# 780-00012-P2_rev3_Sch_M2_Focus_Drive.net
KiCad netlist of a schematic drawn in Altium Designer
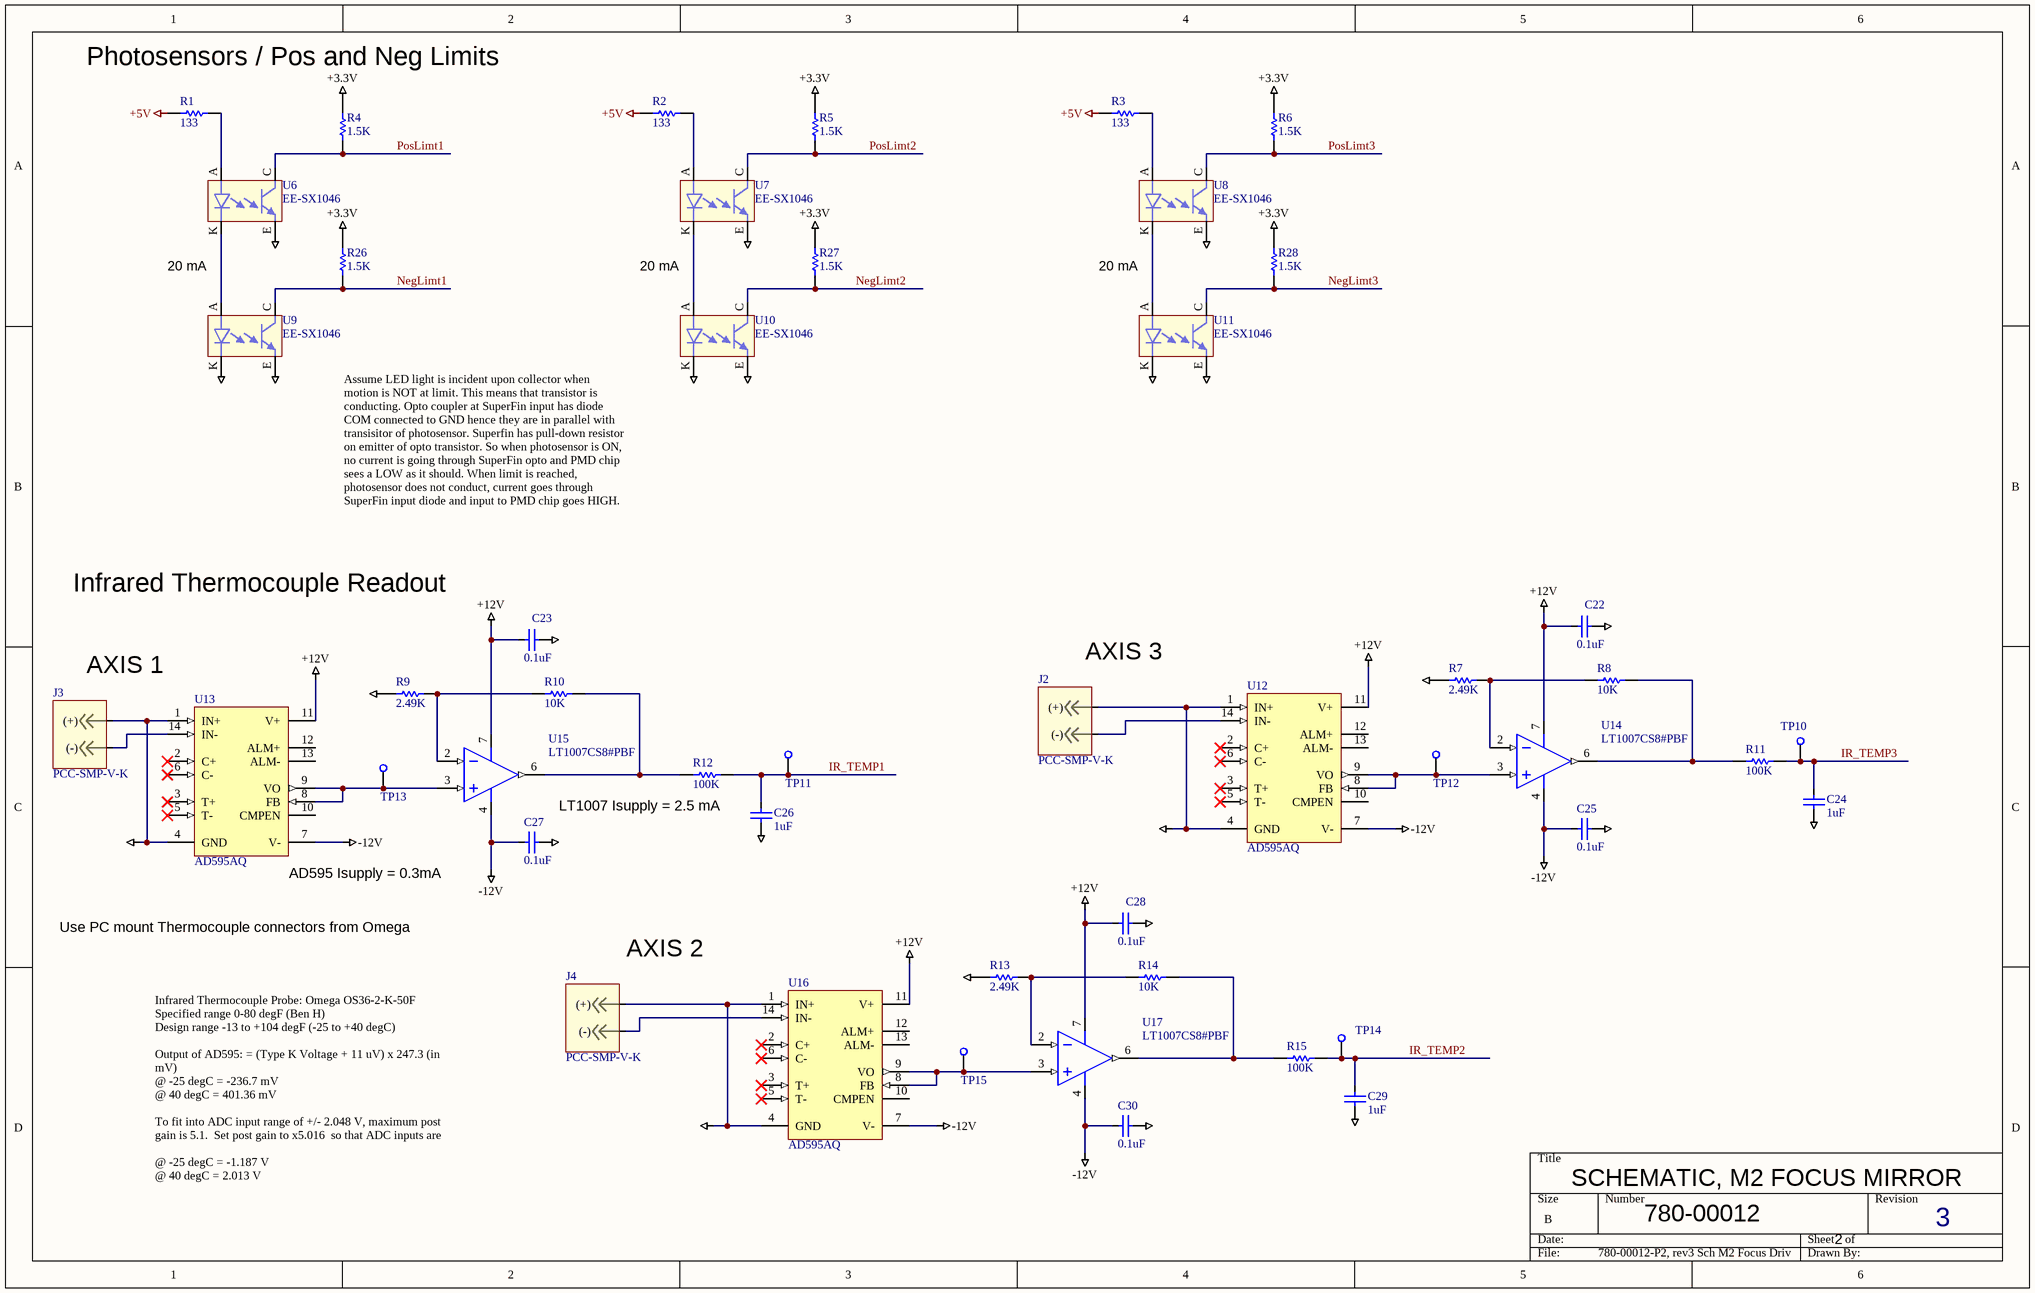
[diagram p0: 780-00012-P2, rev3 Sch M2 Focus Drive.SchDoc]

(export (version "E")
  (design (tool "Eeschema 10.0.6"))
  (components
    (comp (ref "C22")
      (value "0.1uF")
      (footprint "SMD_0805")
      (description "Capacitor")
      (fields (field (name "Comment") "Cap SMD"))
      (libsource (lib "Richs Schematic Components") (part "Cap SMD"))
    )
    (comp (ref "C23")
      (value "0.1uF")
      (footprint "SMD_0805")
      (description "Capacitor")
      (fields (field (name "Comment") "Cap SMD"))
      (libsource (lib "Richs Schematic Components") (part "Cap SMD"))
    )
    (comp (ref "C24")
      (value "1uF")
      (footprint "SMD_0805")
      (description "Capacitor")
      (fields (field (name "Comment") "Cap SMD"))
      (libsource (lib "Richs Schematic Components") (part "Cap SMD"))
    )
    (comp (ref "C25")
      (value "0.1uF")
      (footprint "SMD_0805")
      (description "Capacitor")
      (fields (field (name "Comment") "Cap SMD"))
      (libsource (lib "Richs Schematic Components") (part "Cap SMD"))
    )
    (comp (ref "C26")
      (value "1uF")
      (footprint "SMD_0805")
      (description "Capacitor")
      (fields (field (name "Comment") "Cap SMD"))
      (libsource (lib "Richs Schematic Components") (part "Cap SMD"))
    )
    (comp (ref "C27")
      (value "0.1uF")
      (footprint "SMD_0805")
      (description "Capacitor")
      (fields (field (name "Comment") "Cap SMD"))
      (libsource (lib "Richs Schematic Components") (part "Cap SMD"))
    )
    (comp (ref "C28")
      (value "0.1uF")
      (footprint "SMD_0805")
      (description "Capacitor")
      (fields (field (name "Comment") "Cap SMD"))
      (libsource (lib "Richs Schematic Components") (part "Cap SMD"))
    )
    (comp (ref "C29")
      (value "1uF")
      (footprint "SMD_0805")
      (description "Capacitor")
      (fields (field (name "Comment") "Cap SMD"))
      (libsource (lib "Richs Schematic Components") (part "Cap SMD"))
    )
    (comp (ref "C30")
      (value "0.1uF")
      (footprint "SMD_0805")
      (description "Capacitor")
      (fields (field (name "Comment") "Cap SMD"))
      (libsource (lib "Richs Schematic Components") (part "Cap SMD"))
    )
    (comp (ref "J2")
      (value "PCC-SMP-V-K")
      (footprint "THERMOCOUPLE")
      (description "T/C Conn PCB mount vertical")
      (libsource (lib "Richs Schematic Components") (part "Thermocouple Connector"))
    )
    (comp (ref "J3")
      (value "PCC-SMP-V-K")
      (footprint "THERMOCOUPLE")
      (description "T/C Conn PCB mount vertical")
      (libsource (lib "Richs Schematic Components") (part "Thermocouple Connector"))
    )
    (comp (ref "J4")
      (value "PCC-SMP-V-K")
      (footprint "THERMOCOUPLE")
      (description "T/C Conn PCB mount vertical")
      (libsource (lib "Richs Schematic Components") (part "Thermocouple Connector"))
    )
    (comp (ref "R1")
      (value "133")
      (footprint "SMD_0805")
      (description "Resistor 0805")
      (fields (field (name "MANUFACTURER") "Vishay/Dale") (field (name "Comment") "Res 0805"))
      (libsource (lib "Richs Schematic Components") (part "Res SMD"))
    )
    (comp (ref "R2")
      (value "133")
      (footprint "SMD_0805")
      (description "Resistor 0805")
      (fields (field (name "MANUFACTURER") "Vishay/Dale") (field (name "Comment") "Res 0805"))
      (libsource (lib "Richs Schematic Components") (part "Res SMD"))
    )
    (comp (ref "R3")
      (value "133")
      (footprint "SMD_0805")
      (description "Resistor 0805")
      (fields (field (name "MANUFACTURER") "Vishay/Dale") (field (name "Comment") "Res 0805"))
      (libsource (lib "Richs Schematic Components") (part "Res SMD"))
    )
    (comp (ref "R4")
      (value "1.5K")
      (footprint "SMD_0805")
      (description "Resistor 0805")
      (fields (field (name "MANUFACTURER") "Vishay/Dale") (field (name "Comment") "Res 0805"))
      (libsource (lib "Richs Schematic Components") (part "Res SMD"))
    )
    (comp (ref "R5")
      (value "1.5K")
      (footprint "SMD_0805")
      (description "Resistor 0805")
      (fields (field (name "MANUFACTURER") "Vishay/Dale") (field (name "Comment") "Res 0805"))
      (libsource (lib "Richs Schematic Components") (part "Res SMD"))
    )
    (comp (ref "R6")
      (value "1.5K")
      (footprint "SMD_0805")
      (description "Resistor 0805")
      (fields (field (name "MANUFACTURER") "Vishay/Dale") (field (name "Comment") "Res 0805"))
      (libsource (lib "Richs Schematic Components") (part "Res SMD"))
    )
    (comp (ref "R7")
      (value "2.49K")
      (footprint "SMD_0805")
      (description "Resistor 0805")
      (fields (field (name "MANUFACTURER") "Vishay/Dale") (field (name "Comment") "Res 0805"))
      (libsource (lib "Richs Schematic Components") (part "Res SMD"))
    )
    (comp (ref "R8")
      (value "10K")
      (footprint "SMD_0805")
      (description "Resistor 0805")
      (fields (field (name "MANUFACTURER") "Vishay/Dale") (field (name "Comment") "Res 0805"))
      (libsource (lib "Richs Schematic Components") (part "Res SMD"))
    )
    (comp (ref "R9")
      (value "2.49K")
      (footprint "SMD_0805")
      (description "Resistor 0805")
      (fields (field (name "MANUFACTURER") "Vishay/Dale") (field (name "Comment") "Res 0805"))
      (libsource (lib "Richs Schematic Components") (part "Res SMD"))
    )
    (comp (ref "R10")
      (value "10K")
      (footprint "SMD_0805")
      (description "Resistor 0805")
      (fields (field (name "MANUFACTURER") "Vishay/Dale") (field (name "Comment") "Res 0805"))
      (libsource (lib "Richs Schematic Components") (part "Res SMD"))
    )
    (comp (ref "R11")
      (value "100K")
      (footprint "SMD_0805")
      (description "Resistor 0805")
      (fields (field (name "MANUFACTURER") "Vishay/Dale") (field (name "Comment") "Res 0805"))
      (libsource (lib "Richs Schematic Components") (part "Res SMD"))
    )
    (comp (ref "R12")
      (value "100K")
      (footprint "SMD_0805")
      (description "Resistor 0805")
      (fields (field (name "MANUFACTURER") "Vishay/Dale") (field (name "Comment") "Res 0805"))
      (libsource (lib "Richs Schematic Components") (part "Res SMD"))
    )
    (comp (ref "R13")
      (value "2.49K")
      (footprint "SMD_0805")
      (description "Resistor 0805")
      (fields (field (name "MANUFACTURER") "Vishay/Dale") (field (name "Comment") "Res 0805"))
      (libsource (lib "Richs Schematic Components") (part "Res SMD"))
    )
    (comp (ref "R14")
      (value "10K")
      (footprint "SMD_0805")
      (description "Resistor 0805")
      (fields (field (name "MANUFACTURER") "Vishay/Dale") (field (name "Comment") "Res 0805"))
      (libsource (lib "Richs Schematic Components") (part "Res SMD"))
    )
    (comp (ref "R15")
      (value "100K")
      (footprint "SMD_0805")
      (description "Resistor 0805")
      (fields (field (name "MANUFACTURER") "Vishay/Dale") (field (name "Comment") "Res 0805"))
      (libsource (lib "Richs Schematic Components") (part "Res SMD"))
    )
    (comp (ref "R26")
      (value "1.5K")
      (footprint "SMD_0805")
      (description "Resistor 0805")
      (fields (field (name "MANUFACTURER") "Vishay/Dale") (field (name "Comment") "Res 0805"))
      (libsource (lib "Richs Schematic Components") (part "Res SMD"))
    )
    (comp (ref "R27")
      (value "1.5K")
      (footprint "SMD_0805")
      (description "Resistor 0805")
      (fields (field (name "MANUFACTURER") "Vishay/Dale") (field (name "Comment") "Res 0805"))
      (libsource (lib "Richs Schematic Components") (part "Res SMD"))
    )
    (comp (ref "R28")
      (value "1.5K")
      (footprint "SMD_0805")
      (description "Resistor 0805")
      (fields (field (name "MANUFACTURER") "Vishay/Dale") (field (name "Comment") "Res 0805"))
      (libsource (lib "Richs Schematic Components") (part "Res SMD"))
    )
    (comp (ref "TP10")
      (value "Test Point SMD")
      (footprint "SMD_TEST POINT")
      (description "SMD loop test point")
      (libsource (lib "Richs Schematic Components") (part "Test Point SMD"))
    )
    (comp (ref "TP11")
      (value "Test Point SMD")
      (footprint "SMD_TEST POINT")
      (description "SMD loop test point")
      (libsource (lib "Richs Schematic Components") (part "Test Point SMD"))
    )
    (comp (ref "TP12")
      (value "Test Point SMD")
      (footprint "SMD_TEST POINT")
      (description "SMD loop test point")
      (libsource (lib "Richs Schematic Components") (part "Test Point SMD"))
    )
    (comp (ref "TP13")
      (value "Test Point SMD")
      (footprint "SMD_TEST POINT")
      (description "SMD loop test point")
      (libsource (lib "Richs Schematic Components") (part "Test Point SMD"))
    )
    (comp (ref "TP14")
      (value "Test Point SMD")
      (footprint "SMD_TEST POINT")
      (description "SMD loop test point")
      (libsource (lib "Richs Schematic Components") (part "Test Point SMD"))
    )
    (comp (ref "TP15")
      (value "Test Point SMD")
      (footprint "SMD_TEST POINT")
      (description "SMD loop test point")
      (libsource (lib "Richs Schematic Components") (part "Test Point SMD"))
    )
    (comp (ref "U6")
      (value "EE-SX1046")
      (footprint "Photo-sensor")
      (description "Omron EE-SX1046")
      (libsource (lib "Richs Schematic Components") (part "Photo-sensor"))
    )
    (comp (ref "U7")
      (value "EE-SX1046")
      (footprint "Photo-sensor")
      (description "Omron EE-SX1046")
      (libsource (lib "Richs Schematic Components") (part "Photo-sensor"))
    )
    (comp (ref "U8")
      (value "EE-SX1046")
      (footprint "Photo-sensor")
      (description "Omron EE-SX1046")
      (libsource (lib "Richs Schematic Components") (part "Photo-sensor"))
    )
    (comp (ref "U9")
      (value "EE-SX1046")
      (footprint "Photo-sensor")
      (description "Omron EE-SX1046")
      (libsource (lib "Richs Schematic Components") (part "Photo-sensor"))
    )
    (comp (ref "U10")
      (value "EE-SX1046")
      (footprint "Photo-sensor")
      (description "Omron EE-SX1046")
      (libsource (lib "Richs Schematic Components") (part "Photo-sensor"))
    )
    (comp (ref "U11")
      (value "EE-SX1046")
      (footprint "Photo-sensor")
      (description "Omron EE-SX1046")
      (libsource (lib "Richs Schematic Components") (part "Photo-sensor"))
    )
    (comp (ref "U12")
      (value "AD595AQ")
      (footprint "Q-14_A")
      (description "Monolithic Thermocouple Amplifier with Cold Junction Compensation")
      (fields (field (name "MANUFACTURER") "Analog Devices"))
      (libsource (lib "AD Thermocouple Amplifier") (part "AD595AQ"))
    )
    (comp (ref "U13")
      (value "AD595AQ")
      (footprint "Q-14_A")
      (description "Monolithic Thermocouple Amplifier with Cold Junction Compensation")
      (fields (field (name "MANUFACTURER") "Analog Devices"))
      (libsource (lib "AD Thermocouple Amplifier") (part "AD595AQ"))
    )
    (comp (ref "U14")
      (value "LT1007CS8#PBF")
      (footprint "S8_M")
      (description "Low Noise BJT input opamp")
      (fields (field (name "MANUFACTURER") "Linear Tech"))
      (libsource (lib "Richs Schematic Components") (part "LT1007CS8#PBF"))
    )
    (comp (ref "U15")
      (value "LT1007CS8#PBF")
      (footprint "S8_M")
      (description "Low Noise BJT input opamp")
      (fields (field (name "MANUFACTURER") "Linear Tech"))
      (libsource (lib "Richs Schematic Components") (part "LT1007CS8#PBF"))
    )
    (comp (ref "U16")
      (value "AD595AQ")
      (footprint "Q-14_A")
      (description "Monolithic Thermocouple Amplifier with Cold Junction Compensation")
      (fields (field (name "MANUFACTURER") "Analog Devices"))
      (libsource (lib "AD Thermocouple Amplifier") (part "AD595AQ"))
    )
    (comp (ref "U17")
      (value "LT1007CS8#PBF")
      (footprint "S8_M")
      (description "Low Noise BJT input opamp")
      (fields (field (name "MANUFACTURER") "Linear Tech"))
      (libsource (lib "Richs Schematic Components") (part "LT1007CS8#PBF"))
    )
  )
  (nets
    (net (code "1") (name "+3.3V") (class "Default")
      (node (ref "R26") (pin "2") (pinfunction "2_2") (pintype "passive"))
      (node (ref "R27") (pin "2") (pinfunction "2_2") (pintype "passive"))
      (node (ref "R28") (pin "2") (pinfunction "2_2") (pintype "passive"))
      (node (ref "R4") (pin "2") (pinfunction "2_2") (pintype "passive"))
      (node (ref "R5") (pin "2") (pinfunction "2_2") (pintype "passive"))
      (node (ref "R6") (pin "2") (pinfunction "2_2") (pintype "passive"))
    )
    (net (code "2") (name "+5V") (class "Default")
      (node (ref "R1") (pin "2") (pinfunction "2_2") (pintype "passive"))
      (node (ref "R2") (pin "2") (pinfunction "2_2") (pintype "passive"))
      (node (ref "R3") (pin "2") (pinfunction "2_2") (pintype "passive"))
    )
    (net (code "3") (name "+12V") (class "Default")
      (node (ref "C22") (pin "2") (pinfunction "2_2") (pintype "passive"))
      (node (ref "C23") (pin "2") (pinfunction "2_2") (pintype "passive"))
      (node (ref "C28") (pin "2") (pinfunction "2_2") (pintype "passive"))
      (node (ref "U12") (pin "11") (pinfunction "V+_11") (pintype "power_in"))
      (node (ref "U13") (pin "11") (pinfunction "V+_11") (pintype "power_in"))
      (node (ref "U14") (pin "7") (pinfunction "V+_7") (pintype "power_in"))
      (node (ref "U15") (pin "7") (pinfunction "V+_7") (pintype "power_in"))
      (node (ref "U16") (pin "11") (pinfunction "V+_11") (pintype "power_in"))
      (node (ref "U17") (pin "7") (pinfunction "V+_7") (pintype "power_in"))
    )
    (net (code "4") (name "-12V") (class "Default")
      (node (ref "C25") (pin "2") (pinfunction "2_2") (pintype "passive"))
      (node (ref "C27") (pin "2") (pinfunction "2_2") (pintype "passive"))
      (node (ref "C30") (pin "2") (pinfunction "2_2") (pintype "passive"))
      (node (ref "U12") (pin "7") (pinfunction "V-_7") (pintype "power_in"))
      (node (ref "U13") (pin "7") (pinfunction "V-_7") (pintype "power_in"))
      (node (ref "U14") (pin "4") (pinfunction "V-_4") (pintype "power_in"))
      (node (ref "U15") (pin "4") (pinfunction "V-_4") (pintype "power_in"))
      (node (ref "U16") (pin "7") (pinfunction "V-_7") (pintype "power_in"))
      (node (ref "U17") (pin "4") (pinfunction "V-_4") (pintype "power_in"))
    )
    (net (code "5") (name "/IR_TEMP1") (class "Default")
      (node (ref "C26") (pin "2") (pinfunction "2_2") (pintype "passive"))
      (node (ref "R12") (pin "2") (pinfunction "2_2") (pintype "passive"))
      (node (ref "TP11") (pin "1") (pinfunction "TP_1") (pintype "passive"))
    )
    (net (code "6") (name "/IR_TEMP2") (class "Default")
      (node (ref "C29") (pin "2") (pinfunction "2_2") (pintype "passive"))
      (node (ref "R15") (pin "2") (pinfunction "2_2") (pintype "passive"))
      (node (ref "TP14") (pin "1") (pinfunction "TP_1") (pintype "passive"))
    )
    (net (code "7") (name "/IR_TEMP3") (class "Default")
      (node (ref "C24") (pin "2") (pinfunction "2_2") (pintype "passive"))
      (node (ref "R11") (pin "2") (pinfunction "2_2") (pintype "passive"))
      (node (ref "TP10") (pin "1") (pinfunction "TP_1") (pintype "passive"))
    )
    (net (code "8") (name "/NegLimt1") (class "Default")
      (node (ref "R26") (pin "1") (pinfunction "1_1") (pintype "passive"))
      (node (ref "U9") (pin "C") (pinfunction "collector_C") (pintype "passive"))
    )
    (net (code "9") (name "/NegLimt2") (class "Default")
      (node (ref "R27") (pin "1") (pinfunction "1_1") (pintype "passive"))
      (node (ref "U10") (pin "C") (pinfunction "collector_C") (pintype "passive"))
    )
    (net (code "10") (name "/NegLimt3") (class "Default")
      (node (ref "R28") (pin "1") (pinfunction "1_1") (pintype "passive"))
      (node (ref "U11") (pin "C") (pinfunction "collector_C") (pintype "passive"))
    )
    (net (code "11") (name "/PosLimt1") (class "Default")
      (node (ref "R4") (pin "1") (pinfunction "1_1") (pintype "passive"))
      (node (ref "U6") (pin "C") (pinfunction "collector_C") (pintype "passive"))
    )
    (net (code "12") (name "/PosLimt2") (class "Default")
      (node (ref "R5") (pin "1") (pinfunction "1_1") (pintype "passive"))
      (node (ref "U7") (pin "C") (pinfunction "collector_C") (pintype "passive"))
    )
    (net (code "13") (name "/PosLimt3") (class "Default")
      (node (ref "R6") (pin "1") (pinfunction "1_1") (pintype "passive"))
      (node (ref "U8") (pin "C") (pinfunction "collector_C") (pintype "passive"))
    )
    (net (code "14") (name "GND") (class "Default")
      (node (ref "C22") (pin "1") (pinfunction "1_1") (pintype "passive"))
      (node (ref "C23") (pin "1") (pinfunction "1_1") (pintype "passive"))
      (node (ref "C24") (pin "1") (pinfunction "1_1") (pintype "passive"))
      (node (ref "C25") (pin "1") (pinfunction "1_1") (pintype "passive"))
      (node (ref "C26") (pin "1") (pinfunction "1_1") (pintype "passive"))
      (node (ref "C27") (pin "1") (pinfunction "1_1") (pintype "passive"))
      (node (ref "C28") (pin "1") (pinfunction "1_1") (pintype "passive"))
      (node (ref "C29") (pin "1") (pinfunction "1_1") (pintype "passive"))
      (node (ref "C30") (pin "1") (pinfunction "1_1") (pintype "passive"))
      (node (ref "J2") (pin "1") (pinfunction "(+)_1") (pintype "passive"))
      (node (ref "J3") (pin "1") (pinfunction "(+)_1") (pintype "passive"))
      (node (ref "J4") (pin "1") (pinfunction "(+)_1") (pintype "passive"))
      (node (ref "R13") (pin "1") (pinfunction "1_1") (pintype "passive"))
      (node (ref "R7") (pin "1") (pinfunction "1_1") (pintype "passive"))
      (node (ref "R9") (pin "1") (pinfunction "1_1") (pintype "passive"))
      (node (ref "U10") (pin "E") (pinfunction "emitter_E") (pintype "passive"))
      (node (ref "U10") (pin "K") (pinfunction "cathode_K") (pintype "passive"))
      (node (ref "U11") (pin "E") (pinfunction "emitter_E") (pintype "passive"))
      (node (ref "U11") (pin "K") (pinfunction "cathode_K") (pintype "passive"))
      (node (ref "U12") (pin "1") (pinfunction "IN+_1") (pintype "input"))
      (node (ref "U12") (pin "4") (pinfunction "GND_4") (pintype "power_in"))
      (node (ref "U13") (pin "1") (pinfunction "IN+_1") (pintype "input"))
      (node (ref "U13") (pin "4") (pinfunction "GND_4") (pintype "power_in"))
      (node (ref "U16") (pin "1") (pinfunction "IN+_1") (pintype "input"))
      (node (ref "U16") (pin "4") (pinfunction "GND_4") (pintype "power_in"))
      (node (ref "U6") (pin "E") (pinfunction "emitter_E") (pintype "passive"))
      (node (ref "U7") (pin "E") (pinfunction "emitter_E") (pintype "passive"))
      (node (ref "U8") (pin "E") (pinfunction "emitter_E") (pintype "passive"))
      (node (ref "U9") (pin "E") (pinfunction "emitter_E") (pintype "passive"))
      (node (ref "U9") (pin "K") (pinfunction "cathode_K") (pintype "passive"))
    )
    (net (code "15") (name "Net-(J2-(-))") (class "Default")
      (node (ref "J2") (pin "2") (pinfunction "(-)_2") (pintype "passive"))
      (node (ref "U12") (pin "14") (pinfunction "IN-_14") (pintype "input"))
    )
    (net (code "16") (name "Net-(J3-(-))") (class "Default")
      (node (ref "J3") (pin "2") (pinfunction "(-)_2") (pintype "passive"))
      (node (ref "U13") (pin "14") (pinfunction "IN-_14") (pintype "input"))
    )
    (net (code "17") (name "Net-(J4-(-))") (class "Default")
      (node (ref "J4") (pin "2") (pinfunction "(-)_2") (pintype "passive"))
      (node (ref "U16") (pin "14") (pinfunction "IN-_14") (pintype "input"))
    )
    (net (code "18") (name "Net-(TP12-TP)") (class "Default")
      (node (ref "TP12") (pin "1") (pinfunction "TP_1") (pintype "passive"))
      (node (ref "U12") (pin "8") (pinfunction "FB_8") (pintype "input"))
      (node (ref "U12") (pin "9") (pinfunction "VO_9") (pintype "output"))
      (node (ref "U14") (pin "3") (pinfunction "IN+_3") (pintype "input"))
    )
    (net (code "19") (name "Net-(TP13-TP)") (class "Default")
      (node (ref "TP13") (pin "1") (pinfunction "TP_1") (pintype "passive"))
      (node (ref "U13") (pin "8") (pinfunction "FB_8") (pintype "input"))
      (node (ref "U13") (pin "9") (pinfunction "VO_9") (pintype "output"))
      (node (ref "U15") (pin "3") (pinfunction "IN+_3") (pintype "input"))
    )
    (net (code "20") (name "Net-(TP15-TP)") (class "Default")
      (node (ref "TP15") (pin "1") (pinfunction "TP_1") (pintype "passive"))
      (node (ref "U16") (pin "8") (pinfunction "FB_8") (pintype "input"))
      (node (ref "U16") (pin "9") (pinfunction "VO_9") (pintype "output"))
      (node (ref "U17") (pin "3") (pinfunction "IN+_3") (pintype "input"))
    )
    (net (code "21") (name "Net-(U6-anode)") (class "Default")
      (node (ref "R1") (pin "1") (pinfunction "1_1") (pintype "passive"))
      (node (ref "U6") (pin "A") (pinfunction "anode_A") (pintype "passive"))
    )
    (net (code "22") (name "Net-(U6-cathode)") (class "Default")
      (node (ref "U6") (pin "K") (pinfunction "cathode_K") (pintype "passive"))
      (node (ref "U9") (pin "A") (pinfunction "anode_A") (pintype "passive"))
    )
    (net (code "23") (name "Net-(U7-anode)") (class "Default")
      (node (ref "R2") (pin "1") (pinfunction "1_1") (pintype "passive"))
      (node (ref "U7") (pin "A") (pinfunction "anode_A") (pintype "passive"))
    )
    (net (code "24") (name "Net-(U8-anode)") (class "Default")
      (node (ref "R3") (pin "1") (pinfunction "1_1") (pintype "passive"))
      (node (ref "U8") (pin "A") (pinfunction "anode_A") (pintype "passive"))
    )
    (net (code "25") (name "Net-(U10-anode)") (class "Default")
      (node (ref "U10") (pin "A") (pinfunction "anode_A") (pintype "passive"))
      (node (ref "U7") (pin "K") (pinfunction "cathode_K") (pintype "passive"))
    )
    (net (code "26") (name "Net-(U11-anode)") (class "Default")
      (node (ref "U11") (pin "A") (pinfunction "anode_A") (pintype "passive"))
      (node (ref "U8") (pin "K") (pinfunction "cathode_K") (pintype "passive"))
    )
    (net (code "27") (name "Net-(U14-IN-)") (class "Default")
      (node (ref "R7") (pin "2") (pinfunction "2_2") (pintype "passive"))
      (node (ref "R8") (pin "1") (pinfunction "1_1") (pintype "passive"))
      (node (ref "U14") (pin "2") (pinfunction "IN-_2") (pintype "input"))
    )
    (net (code "28") (name "Net-(U14-OUT)") (class "Default")
      (node (ref "R11") (pin "1") (pinfunction "1_1") (pintype "passive"))
      (node (ref "R8") (pin "2") (pinfunction "2_2") (pintype "passive"))
      (node (ref "U14") (pin "6") (pinfunction "OUT_6") (pintype "output"))
    )
    (net (code "29") (name "Net-(U15-IN-)") (class "Default")
      (node (ref "R10") (pin "1") (pinfunction "1_1") (pintype "passive"))
      (node (ref "R9") (pin "2") (pinfunction "2_2") (pintype "passive"))
      (node (ref "U15") (pin "2") (pinfunction "IN-_2") (pintype "input"))
    )
    (net (code "30") (name "Net-(U15-OUT)") (class "Default")
      (node (ref "R10") (pin "2") (pinfunction "2_2") (pintype "passive"))
      (node (ref "R12") (pin "1") (pinfunction "1_1") (pintype "passive"))
      (node (ref "U15") (pin "6") (pinfunction "OUT_6") (pintype "output"))
    )
    (net (code "31") (name "Net-(U17-IN-)") (class "Default")
      (node (ref "R13") (pin "2") (pinfunction "2_2") (pintype "passive"))
      (node (ref "R14") (pin "1") (pinfunction "1_1") (pintype "passive"))
      (node (ref "U17") (pin "2") (pinfunction "IN-_2") (pintype "input"))
    )
    (net (code "32") (name "Net-(U17-OUT)") (class "Default")
      (node (ref "R14") (pin "2") (pinfunction "2_2") (pintype "passive"))
      (node (ref "R15") (pin "1") (pinfunction "1_1") (pintype "passive"))
      (node (ref "U17") (pin "6") (pinfunction "OUT_6") (pintype "output"))
    )
    (net (code "33") (name "unconnected-(U12-ALM+-Pad12)") (class "Default")
      (node (ref "U12") (pin "12") (pinfunction "ALM+_12") (pintype "passive"))
    )
    (net (code "34") (name "unconnected-(U12-ALM--Pad13)") (class "Default")
      (node (ref "U12") (pin "13") (pinfunction "ALM-_13") (pintype "passive"))
    )
    (net (code "35") (name "unconnected-(U12-C+-Pad2)") (class "Default")
      (node (ref "U12") (pin "2") (pinfunction "C+_2") (pintype "input+no_connect"))
    )
    (net (code "36") (name "unconnected-(U12-C--Pad6)") (class "Default")
      (node (ref "U12") (pin "6") (pinfunction "C-_6") (pintype "input+no_connect"))
    )
    (net (code "37") (name "unconnected-(U12-CMPEN-Pad10)") (class "Default")
      (node (ref "U12") (pin "10") (pinfunction "CMPEN_10") (pintype "passive"))
    )
    (net (code "38") (name "unconnected-(U12-T+-Pad3)") (class "Default")
      (node (ref "U12") (pin "3") (pinfunction "T+_3") (pintype "input+no_connect"))
    )
    (net (code "39") (name "unconnected-(U12-T--Pad5)") (class "Default")
      (node (ref "U12") (pin "5") (pinfunction "T-_5") (pintype "input+no_connect"))
    )
    (net (code "40") (name "unconnected-(U13-ALM+-Pad12)") (class "Default")
      (node (ref "U13") (pin "12") (pinfunction "ALM+_12") (pintype "passive"))
    )
    (net (code "41") (name "unconnected-(U13-ALM--Pad13)") (class "Default")
      (node (ref "U13") (pin "13") (pinfunction "ALM-_13") (pintype "passive"))
    )
    (net (code "42") (name "unconnected-(U13-C+-Pad2)") (class "Default")
      (node (ref "U13") (pin "2") (pinfunction "C+_2") (pintype "input+no_connect"))
    )
    (net (code "43") (name "unconnected-(U13-C--Pad6)") (class "Default")
      (node (ref "U13") (pin "6") (pinfunction "C-_6") (pintype "input+no_connect"))
    )
    (net (code "44") (name "unconnected-(U13-CMPEN-Pad10)") (class "Default")
      (node (ref "U13") (pin "10") (pinfunction "CMPEN_10") (pintype "passive"))
    )
    (net (code "45") (name "unconnected-(U13-T+-Pad3)") (class "Default")
      (node (ref "U13") (pin "3") (pinfunction "T+_3") (pintype "input+no_connect"))
    )
    (net (code "46") (name "unconnected-(U13-T--Pad5)") (class "Default")
      (node (ref "U13") (pin "5") (pinfunction "T-_5") (pintype "input+no_connect"))
    )
    (net (code "47") (name "unconnected-(U14-NC-Pad5)") (class "Default")
      (node (ref "U14") (pin "5") (pinfunction "NC_5") (pintype "passive"))
    )
    (net (code "48") (name "unconnected-(U14-VOSTRIM-Pad1)") (class "Default")
      (node (ref "U14") (pin "1") (pinfunction "VOSTRIM_1") (pintype "passive"))
    )
    (net (code "49") (name "unconnected-(U14-VOSTRIM-Pad8)") (class "Default")
      (node (ref "U14") (pin "8") (pinfunction "VOSTRIM_8") (pintype "passive"))
    )
    (net (code "50") (name "unconnected-(U15-NC-Pad5)") (class "Default")
      (node (ref "U15") (pin "5") (pinfunction "NC_5") (pintype "passive"))
    )
    (net (code "51") (name "unconnected-(U15-VOSTRIM-Pad1)") (class "Default")
      (node (ref "U15") (pin "1") (pinfunction "VOSTRIM_1") (pintype "passive"))
    )
    (net (code "52") (name "unconnected-(U15-VOSTRIM-Pad8)") (class "Default")
      (node (ref "U15") (pin "8") (pinfunction "VOSTRIM_8") (pintype "passive"))
    )
    (net (code "53") (name "unconnected-(U16-ALM+-Pad12)") (class "Default")
      (node (ref "U16") (pin "12") (pinfunction "ALM+_12") (pintype "passive"))
    )
    (net (code "54") (name "unconnected-(U16-ALM--Pad13)") (class "Default")
      (node (ref "U16") (pin "13") (pinfunction "ALM-_13") (pintype "passive"))
    )
    (net (code "55") (name "unconnected-(U16-C+-Pad2)") (class "Default")
      (node (ref "U16") (pin "2") (pinfunction "C+_2") (pintype "input+no_connect"))
    )
    (net (code "56") (name "unconnected-(U16-C--Pad6)") (class "Default")
      (node (ref "U16") (pin "6") (pinfunction "C-_6") (pintype "input+no_connect"))
    )
    (net (code "57") (name "unconnected-(U16-CMPEN-Pad10)") (class "Default")
      (node (ref "U16") (pin "10") (pinfunction "CMPEN_10") (pintype "passive"))
    )
    (net (code "58") (name "unconnected-(U16-T+-Pad3)") (class "Default")
      (node (ref "U16") (pin "3") (pinfunction "T+_3") (pintype "input+no_connect"))
    )
    (net (code "59") (name "unconnected-(U16-T--Pad5)") (class "Default")
      (node (ref "U16") (pin "5") (pinfunction "T-_5") (pintype "input+no_connect"))
    )
    (net (code "60") (name "unconnected-(U17-NC-Pad5)") (class "Default")
      (node (ref "U17") (pin "5") (pinfunction "NC_5") (pintype "passive"))
    )
    (net (code "61") (name "unconnected-(U17-VOSTRIM-Pad1)") (class "Default")
      (node (ref "U17") (pin "1") (pinfunction "VOSTRIM_1") (pintype "passive"))
    )
    (net (code "62") (name "unconnected-(U17-VOSTRIM-Pad8)") (class "Default")
      (node (ref "U17") (pin "8") (pinfunction "VOSTRIM_8") (pintype "passive"))
    )
  )
)
